# schemetic_1.net
KiCad netlist of a schematic drawn in Altium Designer
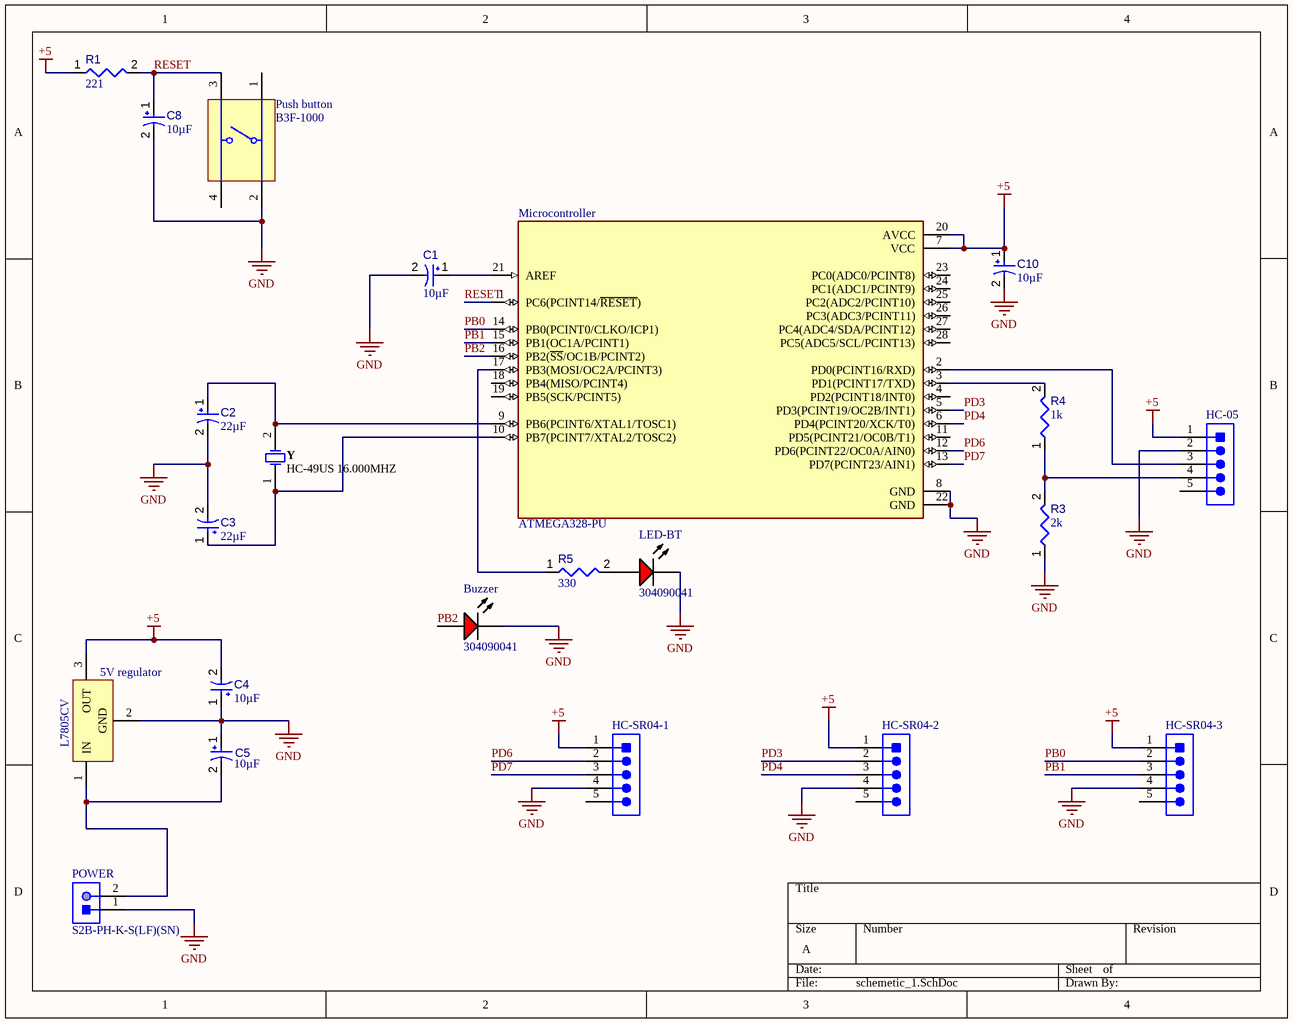
[diagram p0: schemetic_1.SchDoc]

(export (version "E")
  (design (tool "Eeschema 10.0.6"))
  (components
    (comp (ref "5V regulator")
      (value "L7805CV")
      (footprint "TO220")
      (description "Positive Voltage Regulator IC, 1.5 A, 5 V, 0 to 125 degC, 3-Pin TO-220, RoHS, Tube")
      (fields (field (name "MANUFACTURER") "STMicroelectronics"))
      (libsource (lib "University of Moratuwa") (part "PM-REG-L4940-SIL3"))
    )
    (comp (ref "Buzzer")
      (value "304090041")
      (footprint "LED-2P-2.28-3MM_A")
      (description "Red LED, 80 mW, 30 mA, -25 to 85 degC, 2-Pin THD")
      (fields (field (name "MANUFACTURER") "Shenzhen CGX"))
      (libsource (lib "University of Moratuwa") (part "LED-RED-AK-2"))
    )
    (comp (ref "C1")
      (value "10µF")
      (footprint "CAPPR55-200-1100X500X1200")
      (description "Aluminum Electrolytic Capacitor, 10 uF, +/- 20%, 50 V, -40 to 85 degC, 2-Pin THD, RoHS, Bulk")
      (fields (field (name "MANUFACTURER") "Panasonic") (field (name "TOLERANCE") "20%"))
      (libsource (lib "") (part "CAP-P-2_2"))
    )
    (comp (ref "C2")
      (value "22µF")
      (footprint "CAPPR55-250-1120X630X1220")
      (description "Aluminum Electrolytic Capacitor, 22 uF, +/- 20%, 100 V, -40 to 85 degC, 2-Pin THD, RoHS, Bulk")
      (fields (field (name "MANUFACTURER") "Panasonic") (field (name "TOLERANCE") "20%"))
      (libsource (lib "") (part "CAP-P-2_1"))
    )
    (comp (ref "C3")
      (value "22µF")
      (footprint "CAPPR55-250-1120X630X1220")
      (description "Aluminum Electrolytic Capacitor, 22 uF, +/- 20%, 100 V, -40 to 85 degC, 2-Pin THD, RoHS, Bulk")
      (fields (field (name "MANUFACTURER") "Panasonic") (field (name "TOLERANCE") "20%"))
      (libsource (lib "University of Moratuwa") (part "CAP-P-2"))
    )
    (comp (ref "C4")
      (value "10µF")
      (footprint "CAPPR55-200-1100X500X1200")
      (description "Aluminum Electrolytic Capacitor, 10 uF, +/- 20%, 50 V, -40 to 85 degC, 2-Pin THD, RoHS, Bulk")
      (fields (field (name "MANUFACTURER") "Panasonic") (field (name "TOLERANCE") "20%"))
      (libsource (lib "University of Moratuwa") (part "CAP-P-2"))
    )
    (comp (ref "C5")
      (value "10µF")
      (footprint "CAPPR55-200-1100X500X1200")
      (description "Aluminum Electrolytic Capacitor, 10 uF, +/- 20%, 50 V, -40 to 85 degC, 2-Pin THD, RoHS, Bulk")
      (fields (field (name "MANUFACTURER") "Panasonic") (field (name "TOLERANCE") "20%"))
      (libsource (lib "") (part "CAP-P-2_1"))
    )
    (comp (ref "C8")
      (value "10µF")
      (footprint "CAPPR55-200-1100X500X1200")
      (description "Aluminum Electrolytic Capacitor, 10 uF, +/- 20%, 50 V, -40 to 85 degC, 2-Pin THD, RoHS, Bulk")
      (fields (field (name "MANUFACTURER") "Panasonic") (field (name "TOLERANCE") "20%"))
      (libsource (lib "") (part "CAP-P-2_1"))
    )
    (comp (ref "C10")
      (value "10µF")
      (footprint "CAPPR55-200-1100X500X1200")
      (description "Aluminum Electrolytic Capacitor, 10 uF, +/- 20%, 50 V, -40 to 85 degC, 2-Pin THD, RoHS, Bulk")
      (fields (field (name "MANUFACTURER") "Panasonic") (field (name "TOLERANCE") "20%"))
      (libsource (lib "") (part "CAP-P-2_1"))
    )
    (comp (ref "HC-05")
      (value "77311-462K05LF")
      (footprint "FCI-77311-5_V")
      (fields (field (name "MANUFACTURER") "FCI Electronics"))
      (libsource (lib "University of Moratuwa") (part "CN-1P-M-R5"))
    )
    (comp (ref "HC-SR04-1")
      (value "77311-462K05LF")
      (footprint "FCI-77311-5_V")
      (fields (field (name "MANUFACTURER") "FCI Electronics"))
      (libsource (lib "University of Moratuwa") (part "CN-1P-M-R5"))
    )
    (comp (ref "HC-SR04-2")
      (value "77311-462K05LF")
      (footprint "FCI-77311-5_V")
      (fields (field (name "MANUFACTURER") "FCI Electronics"))
      (libsource (lib "University of Moratuwa") (part "CN-1P-M-R5"))
    )
    (comp (ref "HC-SR04-3")
      (value "77311-462K05LF")
      (footprint "FCI-77311-5_V")
      (fields (field (name "MANUFACTURER") "FCI Electronics"))
      (libsource (lib "University of Moratuwa") (part "CN-1P-M-R5"))
    )
    (comp (ref "LED-BT")
      (value "304090041")
      (footprint "LED-2P-2.28-3MM_A")
      (description "Red LED, 80 mW, 30 mA, -25 to 85 degC, 2-Pin THD")
      (fields (field (name "MANUFACTURER") "Shenzhen CGX"))
      (libsource (lib "University of Moratuwa") (part "LED-RED-AK-2"))
    )
    (comp (ref "Microcontroller")
      (value "ATMEGA328-PU")
      (footprint "DIP787W46P254L3467H508Q28")
      (description "AVR AVRÂ® ATmega Microcontroller IC 8-Bit 20MHz 32KB (16K x 16) FLASH 28-PDIP")
      (fields (field (name "MF") "Microchip"))
      (libsource (lib "ATMEGA328-PU") (part "ATMEGA328-PU"))
    )
    (comp (ref "POWER")
      (value "S2B-PH-K-S(LF)(SN)")
      (footprint "JST-S2B-PH-K-S_V")
      (fields (field (name "MANUFACTURER") "Japan Solderless Terminals"))
      (libsource (lib "University of Moratuwa") (part "CN-1P-M-R2"))
    )
    (comp (ref "Push button")
      (value "B3F-1000")
      (footprint "OMRON-B3F-1000-4_V")
      (description "Tactile Switch, SPST-NO, 0.05 A, 24 V, -25 to 70 degC, 4-Pin THD, RoHS, Bulk")
      (fields (field (name "MANUFACTURER") "Omron Electronic Components"))
      (libsource (lib "University of Moratuwa") (part "SW-SPST-4_A"))
    )
    (comp (ref "R1")
      (value "221")
      (footprint "RESA60-630X240")
      (description "Axial Resistor, 221 Ohm, +/- 1%, 250 mW, -55 to 155 degC, 2-Pin THD, RoHS, Bulk")
      (fields (field (name "POWER") "250mW") (field (name "TOLERANCE") "1%"))
      (libsource (lib "University of Moratuwa") (part "RES-2"))
    )
    (comp (ref "R3")
      (value "MFR-25FBF52-1K")
      (footprint "RESA60-630X240")
      (description "Axial Resistor, 1 KOhm, +/- 1%, 250 mW, -55 to 155 degC, 2-Pin THD, RoHS, Bulk")
      (fields (field (name "TOLERANCE") "1%") (field (name "R3") "2k") (field (name "POWER") "250mW"))
      (libsource (lib "University of Moratuwa") (part "RES-2"))
    )
    (comp (ref "R4")
      (value "1k")
      (footprint "RESA60-630X240")
      (description "Axial Resistor, 1 KOhm, +/- 1%, 250 mW, -55 to 155 degC, 2-Pin THD, RoHS, Bulk")
      (fields (field (name "TOLERANCE") "1%") (field (name "POWER") "250mW"))
      (libsource (lib "University of Moratuwa") (part "RES-2"))
    )
    (comp (ref "R5")
      (value "330")
      (footprint "RESA60-630X240")
      (description "Axial Resistor, 1 KOhm, +/- 1%, 250 mW, -55 to 155 degC, 2-Pin THD, RoHS, Bulk")
      (fields (field (name "TOLERANCE") "1%") (field (name "POWER") "250mW"))
      (libsource (lib "University of Moratuwa") (part "RES-2"))
    )
    (comp (ref "Y")
      (value "HC-49US 16.000MHZ")
      (footprint "JPY-HC-49US")
      (description "Crystal, 16 MHz, +/- 30 ppm, 18 pF, -20 to 70 degC, 2-Pin THD")
      (fields (field (name "MANUFACTURER") "Jing peng yuan"))
      (libsource (lib "University of Moratuwa") (part "XTAL-1-2-2"))
    )
  )
  (nets
    (net (code "1") (name "+5") (class "Default")
      (node (ref "5V regulator") (pin "3") (pinfunction "OUT_3") (pintype "power_in"))
      (node (ref "C10") (pin "1") (pinfunction "1_1") (pintype "passive"))
      (node (ref "C4") (pin "2") (pinfunction "2_2") (pintype "passive"))
      (node (ref "HC-05") (pin "1") (pinfunction "DTR_1") (pintype "passive"))
      (node (ref "HC-SR04-1") (pin "1") (pinfunction "DTR_1") (pintype "passive"))
      (node (ref "HC-SR04-2") (pin "1") (pinfunction "DTR_1") (pintype "passive"))
      (node (ref "HC-SR04-3") (pin "1") (pinfunction "DTR_1") (pintype "passive"))
      (node (ref "Microcontroller") (pin "20") (pinfunction "AVCC_20") (pintype "power_in"))
      (node (ref "Microcontroller") (pin "7") (pinfunction "VCC_7") (pintype "power_in"))
      (node (ref "R1") (pin "1") (pinfunction "1_1") (pintype "passive"))
    )
    (net (code "2") (name "/PB0") (class "Default")
      (node (ref "HC-SR04-3") (pin "2") (pinfunction "RXI_2") (pintype "passive"))
      (node (ref "Microcontroller") (pin "14") (pinfunction "PB0(PCINT0/CLKO/ICP1)_14") (pintype "bidirectional"))
    )
    (net (code "3") (name "/PB1") (class "Default")
      (node (ref "HC-SR04-3") (pin "3") (pinfunction "TXO_3") (pintype "passive"))
      (node (ref "Microcontroller") (pin "15") (pinfunction "PB1(OC1A/PCINT1)_15") (pintype "bidirectional"))
    )
    (net (code "4") (name "/PB2") (class "Default")
      (node (ref "Buzzer") (pin "1") (pinfunction "A_1") (pintype "passive"))
      (node (ref "Microcontroller") (pin "16") (pinfunction "PB2(~{SS}/OC1B/PCINT2)_16") (pintype "bidirectional"))
    )
    (net (code "5") (name "/PD3") (class "Default")
      (node (ref "HC-SR04-2") (pin "2") (pinfunction "RXI_2") (pintype "passive"))
      (node (ref "Microcontroller") (pin "5") (pinfunction "PD3(PCINT19/OC2B/INT1)_5") (pintype "bidirectional"))
    )
    (net (code "6") (name "/PD4") (class "Default")
      (node (ref "HC-SR04-2") (pin "3") (pinfunction "TXO_3") (pintype "passive"))
      (node (ref "Microcontroller") (pin "6") (pinfunction "PD4(PCINT20/XCK/T0)_6") (pintype "bidirectional"))
    )
    (net (code "7") (name "/PD6") (class "Default")
      (node (ref "HC-SR04-1") (pin "2") (pinfunction "RXI_2") (pintype "passive"))
      (node (ref "Microcontroller") (pin "12") (pinfunction "PD6(PCINT22/OC0A/AIN0)_12") (pintype "bidirectional"))
    )
    (net (code "8") (name "/PD7") (class "Default")
      (node (ref "HC-SR04-1") (pin "3") (pinfunction "TXO_3") (pintype "passive"))
      (node (ref "Microcontroller") (pin "13") (pinfunction "PD7(PCINT23/AIN1)_13") (pintype "bidirectional"))
    )
    (net (code "9") (name "/RESET") (class "Default")
      (node (ref "C8") (pin "1") (pinfunction "1_1") (pintype "passive"))
      (node (ref "Microcontroller") (pin "1") (pinfunction "PC6(PCINT14/~{RESET})_1") (pintype "bidirectional"))
      (node (ref "Push button") (pin "3") (pinfunction "3_3") (pintype "passive"))
      (node (ref "R1") (pin "2") (pinfunction "2_2") (pintype "passive"))
    )
    (net (code "10") (name "GND") (class "Default")
      (node (ref "5V regulator") (pin "2") (pinfunction "GND_2") (pintype "power_in"))
      (node (ref "Buzzer") (pin "2") (pinfunction "K_2") (pintype "passive"))
      (node (ref "C1") (pin "2") (pinfunction "2_2") (pintype "passive"))
      (node (ref "C10") (pin "2") (pinfunction "2_2") (pintype "passive"))
      (node (ref "C2") (pin "2") (pinfunction "2_2") (pintype "passive"))
      (node (ref "C3") (pin "2") (pinfunction "2_2") (pintype "passive"))
      (node (ref "C4") (pin "1") (pinfunction "1_1") (pintype "passive"))
      (node (ref "C5") (pin "1") (pinfunction "1_1") (pintype "passive"))
      (node (ref "C8") (pin "2") (pinfunction "2_2") (pintype "passive"))
      (node (ref "HC-05") (pin "2") (pinfunction "RXI_2") (pintype "passive"))
      (node (ref "HC-SR04-1") (pin "4") (pinfunction "VCC_4") (pintype "passive"))
      (node (ref "HC-SR04-2") (pin "4") (pinfunction "VCC_4") (pintype "passive"))
      (node (ref "HC-SR04-3") (pin "4") (pinfunction "VCC_4") (pintype "passive"))
      (node (ref "LED-BT") (pin "2") (pinfunction "K_2") (pintype "passive"))
      (node (ref "Microcontroller") (pin "22") (pinfunction "GND_22") (pintype "power_in"))
      (node (ref "Microcontroller") (pin "8") (pinfunction "GND_8") (pintype "power_in"))
      (node (ref "POWER") (pin "1") (pinfunction "1_1") (pintype "passive"))
      (node (ref "Push button") (pin "2") (pinfunction "2_2") (pintype "passive"))
      (node (ref "R3") (pin "1") (pinfunction "1_1") (pintype "passive"))
    )
    (net (code "11") (name "Net-(5V regulator-IN)") (class "Default")
      (node (ref "5V regulator") (pin "1") (pinfunction "IN_1") (pintype "power_in"))
      (node (ref "C5") (pin "2") (pinfunction "2_2") (pintype "passive"))
      (node (ref "POWER") (pin "2") (pinfunction "2_2") (pintype "passive"))
    )
    (net (code "12") (name "Net-(HC-05-TXO)") (class "Default")
      (node (ref "HC-05") (pin "3") (pinfunction "TXO_3") (pintype "passive"))
      (node (ref "Microcontroller") (pin "2") (pinfunction "PD0(PCINT16/RXD)_2") (pintype "bidirectional"))
    )
    (net (code "13") (name "Net-(HC-05-VCC)") (class "Default")
      (node (ref "HC-05") (pin "4") (pinfunction "VCC_4") (pintype "passive"))
      (node (ref "R3") (pin "2") (pinfunction "2_2") (pintype "passive"))
      (node (ref "R4") (pin "1") (pinfunction "1_1") (pintype "passive"))
    )
    (net (code "14") (name "Net-(LED-BT-A)") (class "Default")
      (node (ref "LED-BT") (pin "1") (pinfunction "A_1") (pintype "passive"))
      (node (ref "R5") (pin "2") (pinfunction "2_2") (pintype "passive"))
    )
    (net (code "15") (name "Net-(Microcontroller-AREF)") (class "Default")
      (node (ref "C1") (pin "1") (pinfunction "1_1") (pintype "passive"))
      (node (ref "Microcontroller") (pin "21") (pinfunction "AREF_21") (pintype "input"))
    )
    (net (code "16") (name "Net-(Microcontroller-PB3(MOSI{slash}OC2A{slash}PCINT3))") (class "Default")
      (node (ref "Microcontroller") (pin "17") (pinfunction "PB3(MOSI/OC2A/PCINT3)_17") (pintype "bidirectional"))
      (node (ref "R5") (pin "1") (pinfunction "1_1") (pintype "passive"))
    )
    (net (code "17") (name "Net-(Microcontroller-PB6(PCINT6{slash}XTAL1{slash}TOSC1))") (class "Default")
      (node (ref "C2") (pin "1") (pinfunction "1_1") (pintype "passive"))
      (node (ref "Microcontroller") (pin "9") (pinfunction "PB6(PCINT6/XTAL1/TOSC1)_9") (pintype "bidirectional"))
      (node (ref "Y") (pin "2") (pinfunction "2_2") (pintype "passive"))
    )
    (net (code "18") (name "Net-(Microcontroller-PB7(PCINT7{slash}XTAL2{slash}TOSC2))") (class "Default")
      (node (ref "C3") (pin "1") (pinfunction "1_1") (pintype "passive"))
      (node (ref "Microcontroller") (pin "10") (pinfunction "PB7(PCINT7/XTAL2/TOSC2)_10") (pintype "bidirectional"))
      (node (ref "Y") (pin "1") (pinfunction "1_1") (pintype "passive"))
    )
    (net (code "19") (name "Net-(Microcontroller-PD1(PCINT17{slash}TXD))") (class "Default")
      (node (ref "Microcontroller") (pin "3") (pinfunction "PD1(PCINT17/TXD)_3") (pintype "bidirectional"))
      (node (ref "R4") (pin "2") (pinfunction "2_2") (pintype "passive"))
    )
    (net (code "20") (name "unconnected-(HC-05-CTS-Pad5)") (class "Default")
      (node (ref "HC-05") (pin "5") (pinfunction "CTS_5") (pintype "passive"))
    )
    (net (code "21") (name "unconnected-(HC-SR04-1-CTS-Pad5)") (class "Default")
      (node (ref "HC-SR04-1") (pin "5") (pinfunction "CTS_5") (pintype "passive"))
    )
    (net (code "22") (name "unconnected-(HC-SR04-2-CTS-Pad5)") (class "Default")
      (node (ref "HC-SR04-2") (pin "5") (pinfunction "CTS_5") (pintype "passive"))
    )
    (net (code "23") (name "unconnected-(HC-SR04-3-CTS-Pad5)") (class "Default")
      (node (ref "HC-SR04-3") (pin "5") (pinfunction "CTS_5") (pintype "passive"))
    )
    (net (code "24") (name "unconnected-(Microcontroller-PB4(MISO{slash}PCINT4)-Pad18)") (class "Default")
      (node (ref "Microcontroller") (pin "18") (pinfunction "PB4(MISO/PCINT4)_18") (pintype "bidirectional"))
    )
    (net (code "25") (name "unconnected-(Microcontroller-PB5(SCK{slash}PCINT5)-Pad19)") (class "Default")
      (node (ref "Microcontroller") (pin "19") (pinfunction "PB5(SCK/PCINT5)_19") (pintype "bidirectional"))
    )
    (net (code "26") (name "unconnected-(Microcontroller-PC0(ADC0{slash}PCINT8)-Pad23)") (class "Default")
      (node (ref "Microcontroller") (pin "23") (pinfunction "PC0(ADC0/PCINT8)_23") (pintype "bidirectional"))
    )
    (net (code "27") (name "unconnected-(Microcontroller-PC1(ADC1{slash}PCINT9)-Pad24)") (class "Default")
      (node (ref "Microcontroller") (pin "24") (pinfunction "PC1(ADC1/PCINT9)_24") (pintype "bidirectional"))
    )
    (net (code "28") (name "unconnected-(Microcontroller-PC2(ADC2{slash}PCINT10)-Pad25)") (class "Default")
      (node (ref "Microcontroller") (pin "25") (pinfunction "PC2(ADC2/PCINT10)_25") (pintype "bidirectional"))
    )
    (net (code "29") (name "unconnected-(Microcontroller-PC3(ADC3{slash}PCINT11)-Pad26)") (class "Default")
      (node (ref "Microcontroller") (pin "26") (pinfunction "PC3(ADC3/PCINT11)_26") (pintype "bidirectional"))
    )
    (net (code "30") (name "unconnected-(Microcontroller-PC4(ADC4{slash}SDA{slash}PCINT12)-Pad27)") (class "Default")
      (node (ref "Microcontroller") (pin "27") (pinfunction "PC4(ADC4/SDA/PCINT12)_27") (pintype "bidirectional"))
    )
    (net (code "31") (name "unconnected-(Microcontroller-PC5(ADC5{slash}SCL{slash}PCINT13)-Pad28)") (class "Default")
      (node (ref "Microcontroller") (pin "28") (pinfunction "PC5(ADC5/SCL/PCINT13)_28") (pintype "bidirectional"))
    )
    (net (code "32") (name "unconnected-(Microcontroller-PD2(PCINT18{slash}INT0)-Pad4)") (class "Default")
      (node (ref "Microcontroller") (pin "4") (pinfunction "PD2(PCINT18/INT0)_4") (pintype "bidirectional"))
    )
    (net (code "33") (name "unconnected-(Microcontroller-PD5(PCINT21{slash}OC0B{slash}T1)-Pad11)") (class "Default")
      (node (ref "Microcontroller") (pin "11") (pinfunction "PD5(PCINT21/OC0B/T1)_11") (pintype "bidirectional"))
    )
    (net (code "34") (name "unconnected-(Push button-Pad1)") (class "Default")
      (node (ref "Push button") (pin "1") (pinfunction "1_1") (pintype "passive"))
    )
    (net (code "35") (name "unconnected-(Push button-Pad4)") (class "Default")
      (node (ref "Push button") (pin "4") (pinfunction "4_4") (pintype "passive"))
    )
  )
)
